# Hot_plate.net
KiCad netlist of a schematic drawn in Altium Designer
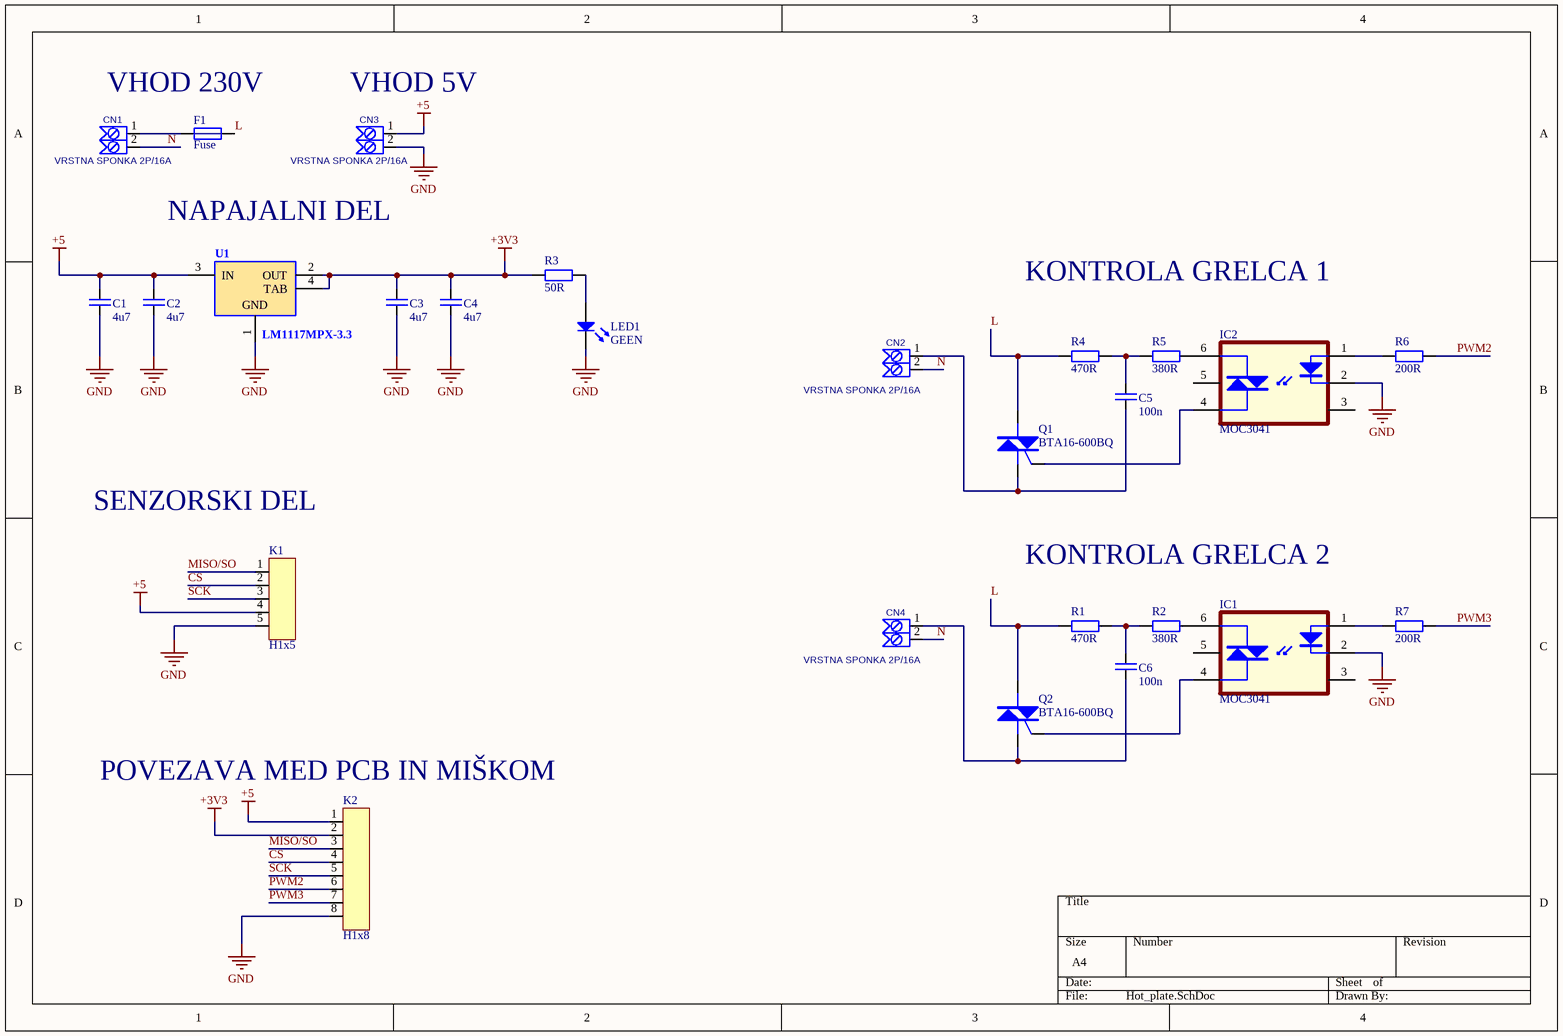
[diagram p0: Hot_plate.SchDoc]

(export (version "E")
  (design (tool "Eeschema 10.0.6"))
  (components
    (comp (ref "C1")
      (value "4u7")
      (footprint "C2012_0805I_M")
      (description "Capacitor")
      (libsource (lib "General") (part "C"))
    )
    (comp (ref "C2")
      (value "4u7")
      (footprint "C2012_0805I_M")
      (description "Capacitor")
      (libsource (lib "General") (part "C"))
    )
    (comp (ref "C3")
      (value "4u7")
      (footprint "C2012_0805I_M")
      (description "Capacitor")
      (libsource (lib "General") (part "C"))
    )
    (comp (ref "C4")
      (value "4u7")
      (footprint "C2012_0805I_M")
      (description "Capacitor")
      (libsource (lib "General") (part "C"))
    )
    (comp (ref "C5")
      (value "100n")
      (footprint "C ceramic F5mm")
      (description "Capacitor")
      (libsource (lib "General") (part "C"))
    )
    (comp (ref "C6")
      (value "100n")
      (footprint "C ceramic F5mm")
      (description "Capacitor")
      (libsource (lib "General") (part "C"))
    )
    (comp (ref "CN1")
      (value "VRSTNA SPONKA 2P/16A")
      (footprint "VRSTNA SPONKA 2P/16A")
      (libsource (lib "Kon_Tipk") (part "VRSTNA SPONKA 2P/16A"))
    )
    (comp (ref "CN2")
      (value "VRSTNA SPONKA 2P/16A")
      (footprint "VRSTNA SPONKA 2P/16A")
      (libsource (lib "Kon_Tipk") (part "VRSTNA SPONKA 2P/16A"))
    )
    (comp (ref "CN3")
      (value "VRSTNA SPONKA 2P/16A")
      (footprint "VRSTNA SPONKA 2P/16A")
      (libsource (lib "Kon_Tipk") (part "VRSTNA SPONKA 2P/16A"))
    )
    (comp (ref "CN4")
      (value "VRSTNA SPONKA 2P/16A")
      (footprint "VRSTNA SPONKA 2P/16A")
      (libsource (lib "Kon_Tipk") (part "VRSTNA SPONKA 2P/16A"))
    )
    (comp (ref "F1") (value "Fuse") (footprint "FUSE-holder") (libsource (lib "Symbols") (part "Fuse")))
    (comp (ref "IC1")
      (value "MOC3041")
      (footprint "DIP-6_L")
      (description "Zero-Cross Oproisolator Triac Driver Output")
      (fields
        (field (name "MANUFACTURER") "FAIRCHILD SEMICONDUCTOR")
        (field (name "MANUFACTURER PART NUMBER") "MOC3041M")
      )
      (libsource (lib "Symbols") (part "MOC3041M"))
    )
    (comp (ref "IC2")
      (value "MOC3041")
      (footprint "DIP-6_L")
      (description "Zero-Cross Oproisolator Triac Driver Output")
      (fields
        (field (name "MANUFACTURER") "FAIRCHILD SEMICONDUCTOR")
        (field (name "MANUFACTURER PART NUMBER") "MOC3041M")
      )
      (libsource (lib "Symbols") (part "MOC3041M"))
    )
    (comp (ref "K1")
      (value "H1x5")
      (footprint "H1x5")
      (description "Header 1x5 (male)")
      (libsource (lib "Kon_Tipk") (part "H1x5"))
    )
    (comp (ref "K2")
      (value "H1x8")
      (footprint "H1x8")
      (description "Header 1x8 (male)")
      (libsource (lib "Kon_Tipk") (part "H1x8"))
    )
    (comp (ref "LED1")
      (value "GEEN")
      (footprint "LED-THT_5")
      (description "L-7104ZGCK")
      (fields (field (name "PUBLISHER") "Altium Limited"))
      (libsource (lib "Symbols") (part "LED"))
    )
    (comp (ref "Q1")
      (value "BTA16-600BQ")
      (footprint "TO-220AB")
      (description "SENSITIVE GATE TRIAC")
      (libsource (lib "Symbols") (part "Triac"))
    )
    (comp (ref "Q2")
      (value "BTA16-600BQ")
      (footprint "TO-220AB")
      (description "SENSITIVE GATE TRIAC")
      (libsource (lib "Symbols") (part "Triac"))
    )
    (comp (ref "R1")
      (value "470R")
      (footprint "R400")
      (description "R")
      (libsource (lib "General") (part "R"))
    )
    (comp (ref "R2")
      (value "380R")
      (footprint "R400")
      (description "R")
      (libsource (lib "General") (part "R"))
    )
    (comp (ref "R3")
      (value "50R")
      (footprint "R2012_0805I_M")
      (description "R")
      (libsource (lib "General") (part "R"))
    )
    (comp (ref "R4")
      (value "470R")
      (footprint "R400")
      (description "R")
      (libsource (lib "General") (part "R"))
    )
    (comp (ref "R5")
      (value "380R")
      (footprint "R400")
      (description "R")
      (libsource (lib "General") (part "R"))
    )
    (comp (ref "R6")
      (value "200R")
      (footprint "R2012_0805I_M")
      (description "R")
      (libsource (lib "General") (part "R"))
    )
    (comp (ref "R7")
      (value "200R")
      (footprint "R2012_0805I_M")
      (description "R")
      (libsource (lib "General") (part "R"))
    )
    (comp (ref "U1")
      (value "LM1117MPX-3.3")
      (footprint "DCY0004A_M")
      (fields
        (field (name "PARTNUMBER") "LM1117MPX-3.3/NOPB")
        (field (name "MANUFACTURER") "Texas Instruments")
      )
      (libsource (lib "MISKO3_V6") (part "LM1117MPX-3.3"))
    )
  )
  (nets
    (net (code "1") (name "+3V3") (class "Default")
      (node (ref "C3") (pin "1") (pinfunction "1_1") (pintype "passive"))
      (node (ref "C4") (pin "1") (pinfunction "1_1") (pintype "passive"))
      (node (ref "K2") (pin "2") (pinfunction "2_2") (pintype "passive"))
      (node (ref "R3") (pin "1") (pintype "passive"))
      (node (ref "U1") (pin "2") (pinfunction "OUT_2") (pintype "power_in"))
      (node (ref "U1") (pin "4") (pinfunction "TAB_4") (pintype "power_in"))
    )
    (net (code "2") (name "+5") (class "Default")
      (node (ref "C1") (pin "1") (pinfunction "1_1") (pintype "passive"))
      (node (ref "C2") (pin "1") (pinfunction "1_1") (pintype "passive"))
      (node (ref "CN3") (pin "1") (pintype "passive"))
      (node (ref "K1") (pin "4") (pinfunction "4_4") (pintype "passive"))
      (node (ref "K2") (pin "1") (pinfunction "1_1") (pintype "passive"))
      (node (ref "U1") (pin "3") (pinfunction "IN_3") (pintype "power_in"))
    )
    (net (code "3") (name "/CS") (class "Default")
      (node (ref "K1") (pin "2") (pinfunction "2_2") (pintype "passive"))
      (node (ref "K2") (pin "4") (pinfunction "4_4") (pintype "passive"))
    )
    (net (code "4") (name "/L") (class "Default")
      (node (ref "F1") (pin "2") (pinfunction "2_2") (pintype "passive"))
      (node (ref "Q1") (pin "2") (pinfunction "M2_2") (pintype "passive"))
      (node (ref "Q2") (pin "2") (pinfunction "M2_2") (pintype "passive"))
      (node (ref "R1") (pin "1") (pintype "passive"))
      (node (ref "R4") (pin "1") (pintype "passive"))
    )
    (net (code "5") (name "/MISO{slash}SO") (class "Default")
      (node (ref "K1") (pin "1") (pinfunction "1_1") (pintype "passive"))
      (node (ref "K2") (pin "3") (pinfunction "3_3") (pintype "passive"))
    )
    (net (code "6") (name "/N") (class "Default")
      (node (ref "CN1") (pin "2") (pintype "passive"))
      (node (ref "CN2") (pin "2") (pintype "passive"))
      (node (ref "CN4") (pin "2") (pintype "passive"))
    )
    (net (code "7") (name "/PWM2") (class "Default")
      (node (ref "K2") (pin "6") (pinfunction "6_6") (pintype "passive"))
      (node (ref "R6") (pin "2") (pintype "passive"))
    )
    (net (code "8") (name "/PWM3") (class "Default")
      (node (ref "K2") (pin "7") (pinfunction "7_7") (pintype "passive"))
      (node (ref "R7") (pin "2") (pintype "passive"))
    )
    (net (code "9") (name "/SCK") (class "Default")
      (node (ref "K1") (pin "3") (pinfunction "3_3") (pintype "passive"))
      (node (ref "K2") (pin "5") (pinfunction "5_5") (pintype "passive"))
    )
    (net (code "10") (name "GND") (class "Default")
      (node (ref "C1") (pin "2") (pinfunction "2_2") (pintype "passive"))
      (node (ref "C2") (pin "2") (pinfunction "2_2") (pintype "passive"))
      (node (ref "C3") (pin "2") (pinfunction "2_2") (pintype "passive"))
      (node (ref "C4") (pin "2") (pinfunction "2_2") (pintype "passive"))
      (node (ref "CN3") (pin "2") (pintype "passive"))
      (node (ref "IC1") (pin "2") (pinfunction "Cathode_2") (pintype "passive"))
      (node (ref "IC2") (pin "2") (pinfunction "Cathode_2") (pintype "passive"))
      (node (ref "K1") (pin "5") (pinfunction "5_5") (pintype "passive"))
      (node (ref "K2") (pin "8") (pinfunction "8_8") (pintype "passive"))
      (node (ref "LED1") (pin "2") (pinfunction "K_2") (pintype "passive"))
      (node (ref "U1") (pin "1") (pinfunction "GND_1") (pintype "power_in"))
    )
    (net (code "11") (name "Net-(C5-Pad1)") (class "Default")
      (node (ref "C5") (pin "1") (pinfunction "1_1") (pintype "passive"))
      (node (ref "R4") (pin "2") (pintype "passive"))
      (node (ref "R5") (pin "1") (pintype "passive"))
    )
    (net (code "12") (name "Net-(C6-Pad1)") (class "Default")
      (node (ref "C6") (pin "1") (pinfunction "1_1") (pintype "passive"))
      (node (ref "R1") (pin "2") (pintype "passive"))
      (node (ref "R2") (pin "1") (pintype "passive"))
    )
    (net (code "13") (name "Net-(CN1-Pad1)") (class "Default")
      (node (ref "CN1") (pin "1") (pintype "passive"))
      (node (ref "F1") (pin "1") (pinfunction "1_1") (pintype "passive"))
    )
    (net (code "14") (name "Net-(IC1-Anode)") (class "Default")
      (node (ref "IC1") (pin "1") (pinfunction "Anode_1") (pintype "passive"))
      (node (ref "R7") (pin "1") (pintype "passive"))
    )
    (net (code "15") (name "Net-(IC1-Main_terminal-Pad6)") (class "Default")
      (node (ref "IC1") (pin "6") (pinfunction "Main_terminal_6") (pintype "passive"))
      (node (ref "R2") (pin "2") (pintype "passive"))
    )
    (net (code "16") (name "Net-(IC2-Anode)") (class "Default")
      (node (ref "IC2") (pin "1") (pinfunction "Anode_1") (pintype "passive"))
      (node (ref "R6") (pin "1") (pintype "passive"))
    )
    (net (code "17") (name "Net-(IC2-Main_terminal-Pad6)") (class "Default")
      (node (ref "IC2") (pin "6") (pinfunction "Main_terminal_6") (pintype "passive"))
      (node (ref "R5") (pin "2") (pintype "passive"))
    )
    (net (code "18") (name "Net-(LED1-A)") (class "Default")
      (node (ref "LED1") (pin "1") (pinfunction "A_1") (pintype "passive"))
      (node (ref "R3") (pin "2") (pintype "passive"))
    )
    (net (code "19") (name "Net-(Q1-G)") (class "Default")
      (node (ref "IC2") (pin "4") (pinfunction "Main_terminal_4") (pintype "passive"))
      (node (ref "Q1") (pin "3") (pinfunction "G_3") (pintype "passive"))
    )
    (net (code "20") (name "Net-(Q1-M1)") (class "Default")
      (node (ref "C5") (pin "2") (pinfunction "2_2") (pintype "passive"))
      (node (ref "CN2") (pin "1") (pintype "passive"))
      (node (ref "Q1") (pin "1") (pinfunction "M1_1") (pintype "passive"))
    )
    (net (code "21") (name "Net-(Q2-G)") (class "Default")
      (node (ref "IC1") (pin "4") (pinfunction "Main_terminal_4") (pintype "passive"))
      (node (ref "Q2") (pin "3") (pinfunction "G_3") (pintype "passive"))
    )
    (net (code "22") (name "Net-(Q2-M1)") (class "Default")
      (node (ref "C6") (pin "2") (pinfunction "2_2") (pintype "passive"))
      (node (ref "CN4") (pin "1") (pintype "passive"))
      (node (ref "Q2") (pin "1") (pinfunction "M1_1") (pintype "passive"))
    )
    (net (code "23") (name "unconnected-(IC1-NC-Pad3)") (class "Default")
      (node (ref "IC1") (pin "3") (pinfunction "NC_3") (pintype "passive"))
    )
    (net (code "24") (name "unconnected-(IC1-Substrate-Pad5)") (class "Default")
      (node (ref "IC1") (pin "5") (pinfunction "Substrate_5") (pintype "passive"))
    )
    (net (code "25") (name "unconnected-(IC2-NC-Pad3)") (class "Default")
      (node (ref "IC2") (pin "3") (pinfunction "NC_3") (pintype "passive"))
    )
    (net (code "26") (name "unconnected-(IC2-Substrate-Pad5)") (class "Default")
      (node (ref "IC2") (pin "5") (pinfunction "Substrate_5") (pintype "passive"))
    )
  )
)
